# Adafruit_2_9in_eInk_FeatherWing.net
KiCad netlist of a schematic drawn in EAGLE
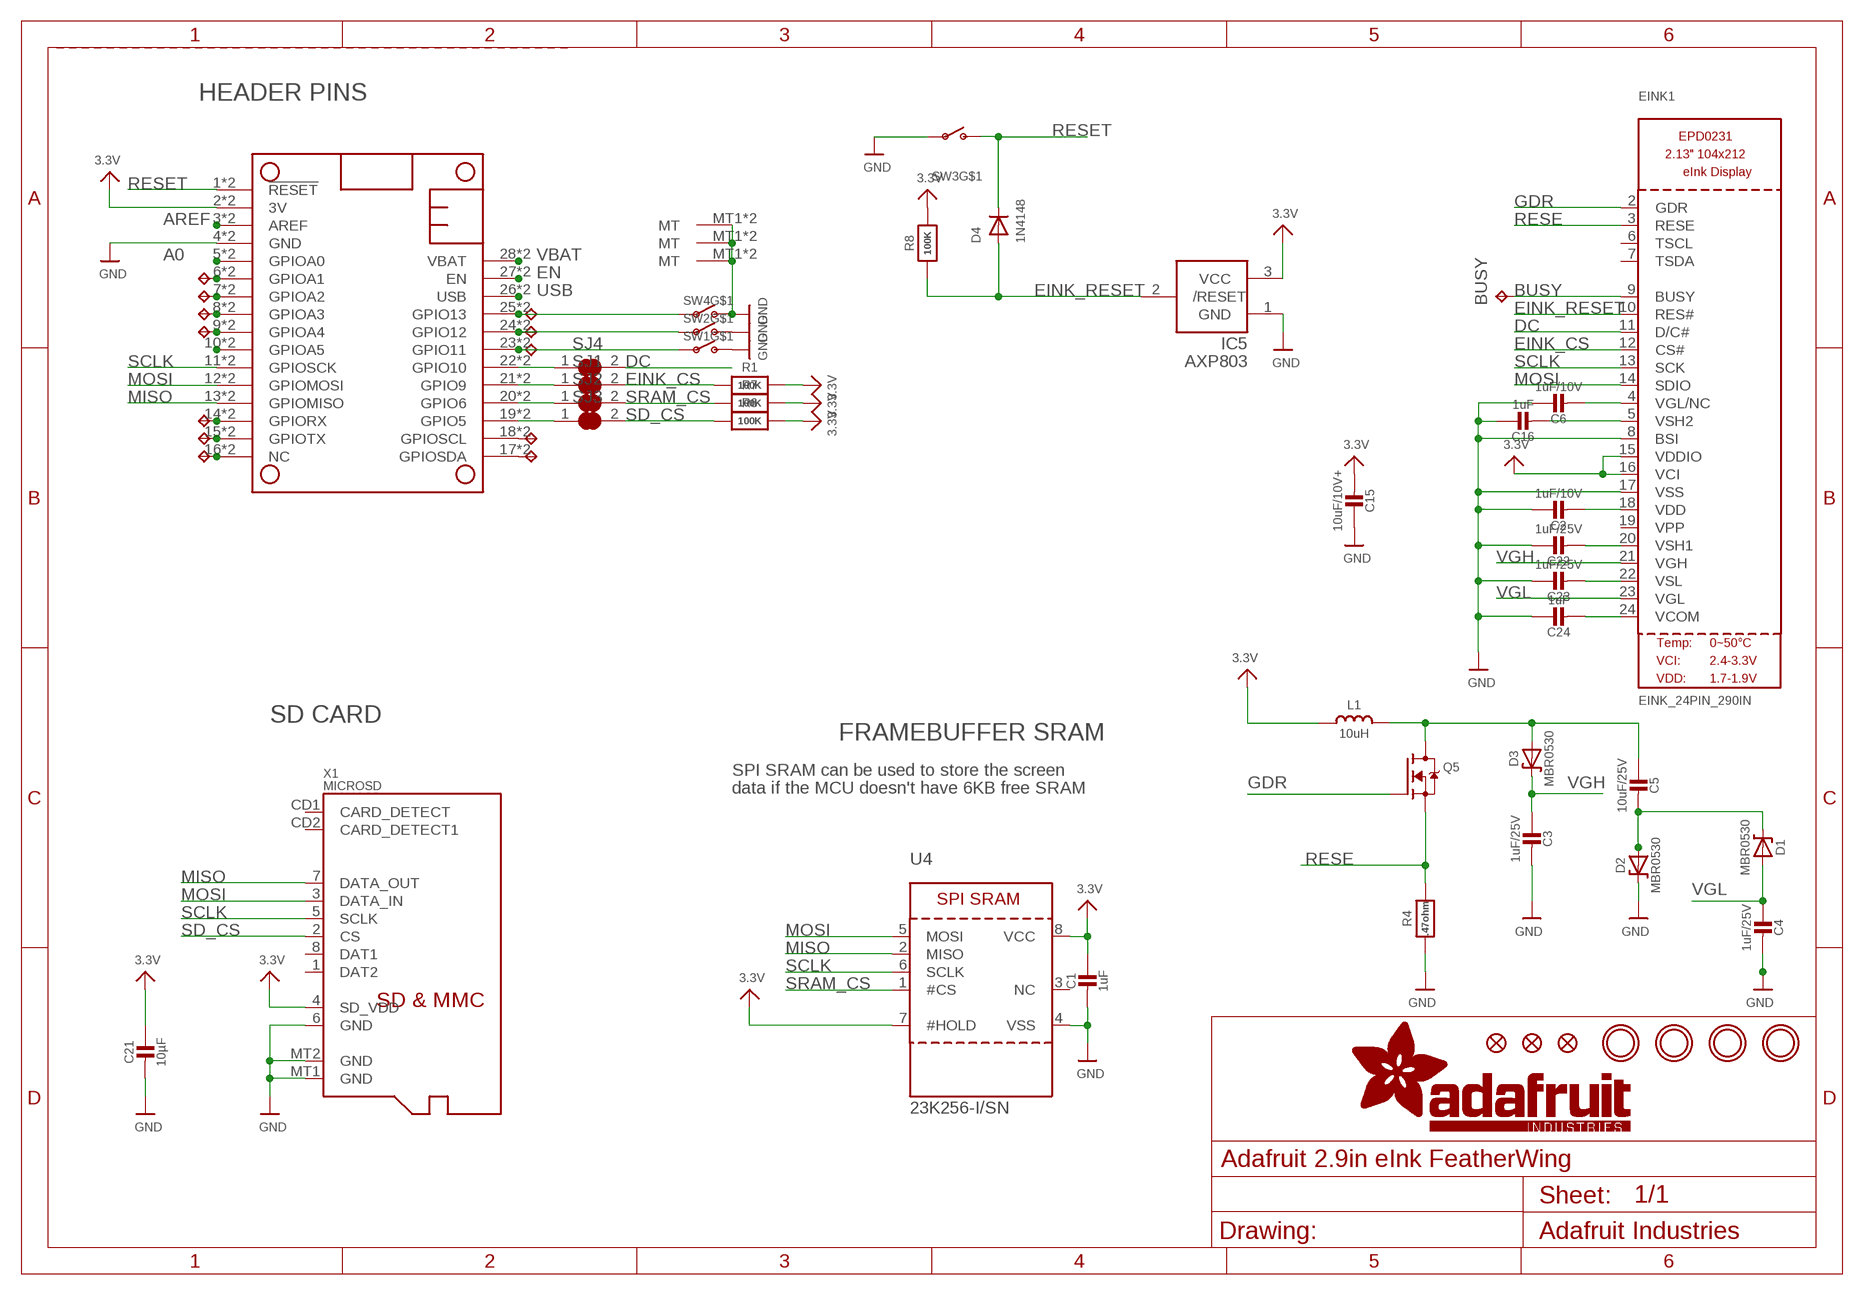
[diagram p0: schematic, sheet 1]

(export (version "E")
  (design (tool "Eeschema 10.0.6"))
  (components
    (comp (ref "BUSY")
      (value "TPTP15SQ")
      (footprint "eagle-import:TP15SQ")
      (libsource (lib "eagle-import") (part "TPTP15SQ"))
    )
    (comp (ref "C1")
      (value "1uF")
      (footprint "eagle-import:0805_10MGAP")
      (fields (field (name "REV") "A"))
      (libsource (lib "eagle-import") (part "CAP_CERAMIC0805_10MGAP"))
    )
    (comp (ref "C2")
      (value "1uF/10V")
      (footprint "eagle-import:0805-NO")
      (libsource (lib "eagle-import") (part "CAP_CERAMIC0805-NOOUTLINE"))
    )
    (comp (ref "C3")
      (value "1uF/25V")
      (footprint "eagle-import:0805-NO")
      (libsource (lib "eagle-import") (part "CAP_CERAMIC0805-NOOUTLINE"))
    )
    (comp (ref "C4")
      (value "1uF/25V")
      (footprint "eagle-import:0805-NO")
      (libsource (lib "eagle-import") (part "CAP_CERAMIC0805-NOOUTLINE"))
    )
    (comp (ref "C5")
      (value "10uF/25V")
      (footprint "eagle-import:0805-NO")
      (libsource (lib "eagle-import") (part "CAP_CERAMIC0805-NOOUTLINE"))
    )
    (comp (ref "C6")
      (value "1uF/10V")
      (footprint "eagle-import:0805-NO")
      (libsource (lib "eagle-import") (part "CAP_CERAMIC0805-NOOUTLINE"))
    )
    (comp (ref "C15")
      (value "10uF/10V+")
      (footprint "eagle-import:0805-NO")
      (libsource (lib "eagle-import") (part "CAP_CERAMIC0805-NOOUTLINE"))
    )
    (comp (ref "C16")
      (value "1uF")
      (footprint "eagle-import:0805-NO")
      (libsource (lib "eagle-import") (part "CAP_CERAMIC0805-NOOUTLINE"))
    )
    (comp (ref "C21")
      (value "10µF")
      (footprint "eagle-import:0805-NO")
      (libsource (lib "eagle-import") (part "CAP_CERAMIC0805-NOOUTLINE"))
    )
    (comp (ref "C22")
      (value "1uF/25V")
      (footprint "eagle-import:0805-NO")
      (libsource (lib "eagle-import") (part "CAP_CERAMIC0805-NOOUTLINE"))
    )
    (comp (ref "C23")
      (value "1uF/25V")
      (footprint "eagle-import:0805-NO")
      (libsource (lib "eagle-import") (part "CAP_CERAMIC0805-NOOUTLINE"))
    )
    (comp (ref "C24")
      (value "1uF")
      (footprint "eagle-import:0805-NO")
      (libsource (lib "eagle-import") (part "CAP_CERAMIC0805-NOOUTLINE"))
    )
    (comp (ref "D1")
      (value "MBR0530")
      (footprint "eagle-import:SOD-123")
      (libsource (lib "eagle-import") (part "DIODE-SCHOTTKYSOD-123"))
    )
    (comp (ref "D2")
      (value "MBR0530")
      (footprint "eagle-import:SOD-123")
      (libsource (lib "eagle-import") (part "DIODE-SCHOTTKYSOD-123"))
    )
    (comp (ref "D3")
      (value "MBR0530")
      (footprint "eagle-import:SOD-123")
      (libsource (lib "eagle-import") (part "DIODE-SCHOTTKYSOD-123"))
    )
    (comp (ref "D4")
      (value "1N4148")
      (footprint "eagle-import:SOD-323F")
      (libsource (lib "eagle-import") (part "DIODESOD-323F"))
    )
    (comp (ref "EINK1")
      (value "EINK_24PIN_290IN")
      (footprint "eagle-import:EINK_290IN")
      (libsource (lib "eagle-import") (part "EINK_24PIN_290IN"))
    )
    (comp (ref "FID1")
      (value "FIDUCIAL_1MM")
      (footprint "eagle-import:FIDUCIAL_1MM")
      (libsource (lib "eagle-import") (part "FIDUCIAL_1MM"))
    )
    (comp (ref "FID2")
      (value "FIDUCIAL_1MM")
      (footprint "eagle-import:FIDUCIAL_1MM")
      (libsource (lib "eagle-import") (part "FIDUCIAL_1MM"))
    )
    (comp (ref "FID3")
      (value "FIDUCIAL_1MM")
      (footprint "eagle-import:FIDUCIAL_1MM")
      (libsource (lib "eagle-import") (part "FIDUCIAL_1MM"))
    )
    (comp (ref "IC5")
      (value "AXP803")
      (footprint "eagle-import:SOT23")
      (libsource (lib "eagle-import") (part "AXP083-SAG"))
    )
    (comp (ref "L1")
      (value "10uH")
      (footprint "eagle-import:INDUCTOR_4X4MM_NR401")
      (libsource (lib "eagle-import") (part "INDUCTORNR401"))
    )
    (comp (ref "MS1")
      (value "FEATHERWING_SMTDUALNOHOLES")
      (footprint "eagle-import:FEATHERWING_SMT_NOHOLES")
      (libsource (lib "eagle-import") (part "FEATHERWING_SMTDUALNOHOLES"))
    )
    (comp (ref "Q5")
      (value "IRLML0100")
      (footprint "eagle-import:SOT23-3")
      (libsource (lib "eagle-import") (part "IRLML2060TRPBF"))
    )
    (comp (ref "R1")
      (value "100K")
      (footprint "eagle-import:0603-NO")
      (libsource (lib "eagle-import") (part "RESISTOR_0603_NOOUT"))
    )
    (comp (ref "R4")
      (value ".47ohm")
      (footprint "eagle-import:0805_10MGAP")
      (libsource (lib "eagle-import") (part "RESISTOR0805_10MGAP"))
    )
    (comp (ref "R6")
      (value "100K")
      (footprint "eagle-import:0603-NO")
      (libsource (lib "eagle-import") (part "RESISTOR_0603_NOOUT"))
    )
    (comp (ref "R7")
      (value "100K")
      (footprint "eagle-import:0603-NO")
      (libsource (lib "eagle-import") (part "RESISTOR_0603_NOOUT"))
    )
    (comp (ref "R8")
      (value "100K")
      (footprint "eagle-import:0603-NO")
      (libsource (lib "eagle-import") (part "RESISTOR_0603_NOOUT"))
    )
    (comp (ref "SJ1")
      (value "SOLDERJUMPER_CLOSED")
      (footprint "eagle-import:SOLDERJUMPER_CLOSEDWIRE")
      (libsource (lib "eagle-import") (part "SOLDERJUMPER_CLOSED"))
    )
    (comp (ref "SJ2")
      (value "SOLDERJUMPER_CLOSED")
      (footprint "eagle-import:SOLDERJUMPER_CLOSEDWIRE")
      (libsource (lib "eagle-import") (part "SOLDERJUMPER_CLOSED"))
    )
    (comp (ref "SJ3")
      (value "SOLDERJUMPER_CLOSED")
      (footprint "eagle-import:SOLDERJUMPER_CLOSEDWIRE")
      (libsource (lib "eagle-import") (part "SOLDERJUMPER_CLOSED"))
    )
    (comp (ref "SJ4")
      (value "SOLDERJUMPER_CLOSED")
      (footprint "eagle-import:SOLDERJUMPER_CLOSEDWIRE")
      (libsource (lib "eagle-import") (part "SOLDERJUMPER_CLOSED"))
    )
    (comp (ref "SW1")
      (value "SWITCH_SPST_TACT_RA")
      (footprint "eagle-import:SPST_TACTILE_RA")
      (libsource (lib "eagle-import") (part "SWITCH_SPST_TACT_RA"))
    )
    (comp (ref "SW2")
      (value "SWITCH_SPST_TACT_RA")
      (footprint "eagle-import:SPST_TACTILE_RA")
      (libsource (lib "eagle-import") (part "SWITCH_SPST_TACT_RA"))
    )
    (comp (ref "SW3")
      (value "SWITCH_SPST_TACT_RA")
      (footprint "eagle-import:SPST_TACTILE_RA")
      (libsource (lib "eagle-import") (part "SWITCH_SPST_TACT_RA"))
    )
    (comp (ref "SW4")
      (value "SWITCH_SPST_TACT_RA")
      (footprint "eagle-import:SPST_TACTILE_RA")
      (libsource (lib "eagle-import") (part "SWITCH_SPST_TACT_RA"))
    )
    (comp (ref "TP1")
      (value "TPTP15SQ")
      (footprint "eagle-import:TP15SQ")
      (libsource (lib "eagle-import") (part "TPTP15SQ"))
    )
    (comp (ref "TP2")
      (value "TPTP15SQ")
      (footprint "eagle-import:TP15SQ")
      (libsource (lib "eagle-import") (part "TPTP15SQ"))
    )
    (comp (ref "TP3")
      (value "TPTP15SQ")
      (footprint "eagle-import:TP15SQ")
      (libsource (lib "eagle-import") (part "TPTP15SQ"))
    )
    (comp (ref "TP4")
      (value "TPTP15SQ")
      (footprint "eagle-import:TP15SQ")
      (libsource (lib "eagle-import") (part "TPTP15SQ"))
    )
    (comp (ref "TP5")
      (value "TPTP15SQ")
      (footprint "eagle-import:TP15SQ")
      (libsource (lib "eagle-import") (part "TPTP15SQ"))
    )
    (comp (ref "TP6")
      (value "TPTP15SQ")
      (footprint "eagle-import:TP15SQ")
      (libsource (lib "eagle-import") (part "TPTP15SQ"))
    )
    (comp (ref "TP7")
      (value "TPTP15SQ")
      (footprint "eagle-import:TP15SQ")
      (libsource (lib "eagle-import") (part "TPTP15SQ"))
    )
    (comp (ref "TP8")
      (value "TPTP15SQ")
      (footprint "eagle-import:TP15SQ")
      (libsource (lib "eagle-import") (part "TPTP15SQ"))
    )
    (comp (ref "TP9")
      (value "TPTP15SQ")
      (footprint "eagle-import:TP15SQ")
      (libsource (lib "eagle-import") (part "TPTP15SQ"))
    )
    (comp (ref "TP11")
      (value "TPTP15SQ")
      (footprint "eagle-import:TP15SQ")
      (libsource (lib "eagle-import") (part "TPTP15SQ"))
    )
    (comp (ref "TP12")
      (value "TPTP15SQ")
      (footprint "eagle-import:TP15SQ")
      (libsource (lib "eagle-import") (part "TPTP15SQ"))
    )
    (comp (ref "TP13")
      (value "TPTP15SQ")
      (footprint "eagle-import:TP15SQ")
      (libsource (lib "eagle-import") (part "TPTP15SQ"))
    )
    (comp (ref "U$3")
      (value "MOUNTINGHOLE2.5")
      (footprint "eagle-import:MOUNTINGHOLE_2.5_PLATED")
      (libsource (lib "eagle-import") (part "MOUNTINGHOLE2.5"))
    )
    (comp (ref "U$4")
      (value "MOUNTINGHOLE2.5")
      (footprint "eagle-import:MOUNTINGHOLE_2.5_PLATED")
      (libsource (lib "eagle-import") (part "MOUNTINGHOLE2.5"))
    )
    (comp (ref "U$5")
      (value "MOUNTINGHOLE2.5")
      (footprint "eagle-import:MOUNTINGHOLE_2.5_PLATED")
      (libsource (lib "eagle-import") (part "MOUNTINGHOLE2.5"))
    )
    (comp (ref "U$6")
      (value "MOUNTINGHOLE2.5")
      (footprint "eagle-import:MOUNTINGHOLE_2.5_PLATED")
      (libsource (lib "eagle-import") (part "MOUNTINGHOLE2.5"))
    )
    (comp (ref "U4")
      (value "23K256-I/SN")
      (footprint "eagle-import:SOIC8_150MIL")
      (libsource (lib "eagle-import") (part "SRAM_SPI_SOIC8"))
    )
    (comp (ref "X1")
      (value "MICROSD")
      (footprint "eagle-import:MICROSD")
      (libsource (lib "eagle-import") (part "MICROSD"))
    )
  )
  (nets
    (net (code "3") (name "/A0") (class "Default")
      (node (ref "MS1") (pin "5") (pinfunction "GPIOA0_5") (pintype "bidirectional"))
      (node (ref "MS1") (pin "5B") (pinfunction "GPIOA0_5B") (pintype "bidirectional"))
    )
    (net (code "4") (name "/AREF") (class "Default")
      (node (ref "MS1") (pin "3") (pinfunction "AREF_3") (pintype "passive"))
      (node (ref "MS1") (pin "3B") (pinfunction "AREF_3B") (pintype "passive"))
    )
    (net (code "5") (name "/BUSY") (class "Default")
      (node (ref "BUSY") (pin "TP") (pinfunction "TP_TP") (pintype "input"))
      (node (ref "EINK1") (pin "9") (pinfunction "BUSY_9") (pintype "output"))
    )
    (net (code "6") (name "/DC") (class "Default")
      (node (ref "EINK1") (pin "11") (pinfunction "D/C#_11") (pintype "input"))
      (node (ref "SJ4") (pin "2") (pinfunction "2_2") (pintype "passive"))
    )
    (net (code "8") (name "/EINK_CS") (class "Default")
      (node (ref "EINK1") (pin "12") (pinfunction "CS#_12") (pintype "input"))
      (node (ref "R1") (pin "1") (pinfunction "1_1") (pintype "passive"))
      (node (ref "SJ1") (pin "2") (pinfunction "2_2") (pintype "passive"))
    )
    (net (code "9") (name "/EINK_RESET") (class "Default")
      (node (ref "D4") (pin "A") (pinfunction "A_A") (pintype "passive"))
      (node (ref "EINK1") (pin "10") (pinfunction "RES#_10") (pintype "input"))
      (node (ref "IC5") (pin "2") (pinfunction "/RESET_2") (pintype "output"))
      (node (ref "R8") (pin "1") (pinfunction "1_1") (pintype "passive"))
    )
    (net (code "10") (name "/EN") (class "Default")
      (node (ref "MS1") (pin "27") (pinfunction "EN_27") (pintype "passive"))
      (node (ref "MS1") (pin "27B") (pinfunction "EN_27B") (pintype "passive"))
    )
    (net (code "11") (name "/GDR") (class "Default")
      (node (ref "EINK1") (pin "2") (pinfunction "GDR_2") (pintype "output"))
      (node (ref "Q5") (pin "1") (pinfunction "G_1") (pintype "bidirectional"))
    )
    (net (code "12") (name "/MISO") (class "Default")
      (node (ref "MS1") (pin "13") (pinfunction "GPIOMISO_13") (pintype "bidirectional"))
      (node (ref "MS1") (pin "13B") (pinfunction "GPIOMISO_13B") (pintype "bidirectional"))
      (node (ref "U4") (pin "2") (pinfunction "MISO_2") (pintype "output"))
      (node (ref "X1") (pin "7") (pinfunction "DATA_OUT_7") (pintype "output"))
    )
    (net (code "13") (name "/MOSI") (class "Default")
      (node (ref "EINK1") (pin "14") (pinfunction "SDIO_14") (pintype "bidirectional"))
      (node (ref "MS1") (pin "12") (pinfunction "GPIOMOSI_12") (pintype "bidirectional"))
      (node (ref "MS1") (pin "12B") (pinfunction "GPIOMOSI_12B") (pintype "bidirectional"))
      (node (ref "U4") (pin "5") (pinfunction "MOSI_5") (pintype "input"))
      (node (ref "X1") (pin "3") (pinfunction "DATA_IN_3") (pintype "input"))
    )
    (net (code "14") (name "/RESE") (class "Default")
      (node (ref "EINK1") (pin "3") (pinfunction "RESE_3") (pintype "input"))
      (node (ref "Q5") (pin "2") (pinfunction "S_2") (pintype "bidirectional"))
      (node (ref "R4") (pin "1") (pinfunction "1_1") (pintype "passive"))
    )
    (net (code "15") (name "/RESET") (class "Default")
      (node (ref "D4") (pin "C") (pinfunction "C_C") (pintype "passive"))
      (node (ref "MS1") (pin "1") (pinfunction "~{RESET}_1") (pintype "input"))
      (node (ref "MS1") (pin "1B") (pinfunction "~{RESET}_1B") (pintype "input"))
      (node (ref "SW3") (pin "2") (pinfunction "S_2") (pintype "passive"))
    )
    (net (code "18") (name "/SCLK") (class "Default")
      (node (ref "EINK1") (pin "13") (pinfunction "SCK_13") (pintype "bidirectional"))
      (node (ref "MS1") (pin "11") (pinfunction "GPIOSCK_11") (pintype "bidirectional"))
      (node (ref "MS1") (pin "11B") (pinfunction "GPIOSCK_11B") (pintype "bidirectional"))
      (node (ref "U4") (pin "6") (pinfunction "SCLK_6") (pintype "input"))
      (node (ref "X1") (pin "5") (pinfunction "SCLK_5") (pintype "input"))
    )
    (net (code "19") (name "/SD_CS") (class "Default")
      (node (ref "R6") (pin "1") (pinfunction "1_1") (pintype "passive"))
      (node (ref "SJ3") (pin "2") (pinfunction "2_2") (pintype "passive"))
      (node (ref "X1") (pin "2") (pinfunction "CS_2") (pintype "input"))
    )
    (net (code "20") (name "/SRAM_CS") (class "Default")
      (node (ref "R7") (pin "1") (pinfunction "1_1") (pintype "passive"))
      (node (ref "SJ2") (pin "2") (pinfunction "2_2") (pintype "passive"))
      (node (ref "U4") (pin "1") (pinfunction "#CS_1") (pintype "input"))
    )
    (net (code "21") (name "/USB") (class "Default")
      (node (ref "MS1") (pin "26") (pinfunction "USB_26") (pintype "power_in"))
      (node (ref "MS1") (pin "26B") (pinfunction "USB_26B") (pintype "power_in"))
    )
    (net (code "22") (name "/VBAT") (class "Default")
      (node (ref "MS1") (pin "28") (pinfunction "VBAT_28") (pintype "power_in"))
      (node (ref "MS1") (pin "28B") (pinfunction "VBAT_28B") (pintype "power_in"))
    )
    (net (code "23") (name "/VGH") (class "Default")
      (node (ref "C3") (pin "1") (pinfunction "1_1") (pintype "passive"))
      (node (ref "D3") (pin "C") (pinfunction "C_C") (pintype "passive"))
      (node (ref "EINK1") (pin "21") (pinfunction "VGH_21") (pintype "passive"))
    )
    (net (code "24") (name "/VGL") (class "Default")
      (node (ref "C4") (pin "1") (pinfunction "1_1") (pintype "passive"))
      (node (ref "D1") (pin "A") (pinfunction "A_A") (pintype "passive"))
      (node (ref "EINK1") (pin "23") (pinfunction "VGL_23") (pintype "passive"))
    )
    (net (code "25") (name "3.3V") (class "Default")
      (node (ref "C1") (pin "1") (pinfunction "1_1") (pintype "passive"))
      (node (ref "C15") (pin "2") (pinfunction "2_2") (pintype "passive"))
      (node (ref "C21") (pin "1") (pinfunction "1_1") (pintype "passive"))
      (node (ref "EINK1") (pin "15") (pinfunction "VDDIO_15") (pintype "power_in"))
      (node (ref "EINK1") (pin "16") (pinfunction "VCI_16") (pintype "power_in"))
      (node (ref "IC5") (pin "3") (pinfunction "VCC_3") (pintype "power_in"))
      (node (ref "L1") (pin "P$2") (pinfunction "2_P$2") (pintype "passive"))
      (node (ref "MS1") (pin "2") (pinfunction "3V_2") (pintype "power_in"))
      (node (ref "MS1") (pin "2B") (pinfunction "3V_2B") (pintype "power_in"))
      (node (ref "R1") (pin "2") (pinfunction "2_2") (pintype "passive"))
      (node (ref "R6") (pin "2") (pinfunction "2_2") (pintype "passive"))
      (node (ref "R7") (pin "2") (pinfunction "2_2") (pintype "passive"))
      (node (ref "R8") (pin "2") (pinfunction "2_2") (pintype "passive"))
      (node (ref "U4") (pin "7") (pinfunction "#HOLD_7") (pintype "input"))
      (node (ref "U4") (pin "8") (pinfunction "VCC_8") (pintype "power_in"))
      (node (ref "X1") (pin "4") (pinfunction "SD_VDD_4") (pintype "power_in"))
    )
    (net (code "26") (name "GND") (class "Default")
      (node (ref "C1") (pin "2") (pinfunction "2_2") (pintype "passive"))
      (node (ref "C15") (pin "1") (pinfunction "1_1") (pintype "passive"))
      (node (ref "C16") (pin "1") (pinfunction "1_1") (pintype "passive"))
      (node (ref "C2") (pin "1") (pinfunction "1_1") (pintype "passive"))
      (node (ref "C21") (pin "2") (pinfunction "2_2") (pintype "passive"))
      (node (ref "C22") (pin "1") (pinfunction "1_1") (pintype "passive"))
      (node (ref "C23") (pin "1") (pinfunction "1_1") (pintype "passive"))
      (node (ref "C24") (pin "1") (pinfunction "1_1") (pintype "passive"))
      (node (ref "C3") (pin "2") (pinfunction "2_2") (pintype "passive"))
      (node (ref "C4") (pin "2") (pinfunction "2_2") (pintype "passive"))
      (node (ref "C6") (pin "1") (pinfunction "1_1") (pintype "passive"))
      (node (ref "D2") (pin "C") (pinfunction "C_C") (pintype "passive"))
      (node (ref "EINK1") (pin "17") (pinfunction "VSS_17") (pintype "power_in"))
      (node (ref "EINK1") (pin "8") (pinfunction "BSI_8") (pintype "input"))
      (node (ref "IC5") (pin "1") (pinfunction "GND_1") (pintype "power_in"))
      (node (ref "MS1") (pin "4") (pinfunction "GND_4") (pintype "power_in"))
      (node (ref "MS1") (pin "4B") (pinfunction "GND_4B") (pintype "power_in"))
      (node (ref "R4") (pin "2") (pinfunction "2_2") (pintype "passive"))
      (node (ref "SW1") (pin "2") (pinfunction "S_2") (pintype "passive"))
      (node (ref "SW1") (pin "MT1") (pinfunction "MT_MT1") (pintype "bidirectional"))
      (node (ref "SW1") (pin "MT2") (pinfunction "MT_MT2") (pintype "bidirectional"))
      (node (ref "SW2") (pin "2") (pinfunction "S_2") (pintype "passive"))
      (node (ref "SW2") (pin "MT1") (pinfunction "MT_MT1") (pintype "bidirectional"))
      (node (ref "SW2") (pin "MT2") (pinfunction "MT_MT2") (pintype "bidirectional"))
      (node (ref "SW3") (pin "1") (pinfunction "P_1") (pintype "passive"))
      (node (ref "SW4") (pin "2") (pinfunction "S_2") (pintype "passive"))
      (node (ref "SW4") (pin "MT1") (pinfunction "MT_MT1") (pintype "bidirectional"))
      (node (ref "SW4") (pin "MT2") (pinfunction "MT_MT2") (pintype "bidirectional"))
      (node (ref "U4") (pin "4") (pinfunction "VSS_4") (pintype "power_in"))
      (node (ref "X1") (pin "6") (pinfunction "GND_6") (pintype "power_in"))
      (node (ref "X1") (pin "MT1") (pinfunction "GND_MT1") (pintype "power_in"))
      (node (ref "X1") (pin "MT2") (pinfunction "GND_MT2") (pintype "power_in"))
    )
    (net (code "27") (name "Net-(C5-Pad2)") (class "Default")
      (node (ref "C5") (pin "2") (pinfunction "2_2") (pintype "passive"))
      (node (ref "D1") (pin "C") (pinfunction "C_C") (pintype "passive"))
      (node (ref "D2") (pin "A") (pinfunction "A_A") (pintype "passive"))
    )
    (net (code "28") (name "Net-(EINK1-VCOM)") (class "Default")
      (node (ref "C24") (pin "2") (pinfunction "2_2") (pintype "passive"))
      (node (ref "EINK1") (pin "24") (pinfunction "VCOM_24") (pintype "passive"))
    )
    (net (code "29") (name "Net-(EINK1-VDD)") (class "Default")
      (node (ref "C2") (pin "2") (pinfunction "2_2") (pintype "passive"))
      (node (ref "EINK1") (pin "18") (pinfunction "VDD_18") (pintype "passive"))
    )
    (net (code "30") (name "Net-(EINK1-VGL{slash}NC)") (class "Default")
      (node (ref "C6") (pin "2") (pinfunction "2_2") (pintype "passive"))
      (node (ref "EINK1") (pin "4") (pinfunction "VGL/NC_4") (pintype "bidirectional"))
    )
    (net (code "31") (name "Net-(EINK1-VSH1)") (class "Default")
      (node (ref "C22") (pin "2") (pinfunction "2_2") (pintype "passive"))
      (node (ref "EINK1") (pin "20") (pinfunction "VSH1_20") (pintype "passive"))
    )
    (net (code "32") (name "Net-(EINK1-VSH2)") (class "Default")
      (node (ref "C16") (pin "2") (pinfunction "2_2") (pintype "passive"))
      (node (ref "EINK1") (pin "5") (pinfunction "VSH2_5") (pintype "passive"))
    )
    (net (code "33") (name "Net-(EINK1-VSL)") (class "Default")
      (node (ref "C23") (pin "2") (pinfunction "2_2") (pintype "passive"))
      (node (ref "EINK1") (pin "22") (pinfunction "VSL_22") (pintype "passive"))
    )
    (net (code "34") (name "Net-(L1-1)") (class "Default")
      (node (ref "C5") (pin "1") (pinfunction "1_1") (pintype "passive"))
      (node (ref "D3") (pin "A") (pinfunction "A_A") (pintype "passive"))
      (node (ref "L1") (pin "P$1") (pinfunction "1_P$1") (pintype "passive"))
      (node (ref "Q5") (pin "3") (pinfunction "D_3") (pintype "bidirectional"))
    )
    (net (code "35") (name "Net-(MS1-GPIO5-Pad19)") (class "Default")
      (node (ref "MS1") (pin "19") (pinfunction "GPIO5_19") (pintype "bidirectional"))
      (node (ref "MS1") (pin "19B") (pinfunction "GPIO5_19B") (pintype "bidirectional"))
      (node (ref "SJ3") (pin "1") (pinfunction "1_1") (pintype "passive"))
    )
    (net (code "36") (name "Net-(MS1-GPIO6-Pad20)") (class "Default")
      (node (ref "MS1") (pin "20") (pinfunction "GPIO6_20") (pintype "bidirectional"))
      (node (ref "MS1") (pin "20B") (pinfunction "GPIO6_20B") (pintype "bidirectional"))
      (node (ref "SJ2") (pin "1") (pinfunction "1_1") (pintype "passive"))
    )
    (net (code "37") (name "Net-(MS1-GPIO9-Pad21)") (class "Default")
      (node (ref "MS1") (pin "21") (pinfunction "GPIO9_21") (pintype "bidirectional"))
      (node (ref "MS1") (pin "21B") (pinfunction "GPIO9_21B") (pintype "bidirectional"))
      (node (ref "SJ1") (pin "1") (pinfunction "1_1") (pintype "passive"))
    )
    (net (code "38") (name "Net-(MS1-GPIO10-Pad22)") (class "Default")
      (node (ref "MS1") (pin "22") (pinfunction "GPIO10_22") (pintype "bidirectional"))
      (node (ref "MS1") (pin "22B") (pinfunction "GPIO10_22B") (pintype "bidirectional"))
      (node (ref "SJ4") (pin "1") (pinfunction "1_1") (pintype "passive"))
    )
    (net (code "39") (name "Net-(MS1-GPIOA1-Pad6)") (class "Default")
      (node (ref "MS1") (pin "6") (pinfunction "GPIOA1_6") (pintype "bidirectional"))
      (node (ref "MS1") (pin "6B") (pinfunction "GPIOA1_6B") (pintype "bidirectional"))
      (node (ref "TP6") (pin "TP") (pinfunction "TP_TP") (pintype "input"))
    )
    (net (code "40") (name "Net-(MS1-GPIOA2-Pad7)") (class "Default")
      (node (ref "MS1") (pin "7") (pinfunction "GPIOA2_7") (pintype "bidirectional"))
      (node (ref "MS1") (pin "7B") (pinfunction "GPIOA2_7B") (pintype "bidirectional"))
      (node (ref "TP7") (pin "TP") (pinfunction "TP_TP") (pintype "input"))
    )
    (net (code "41") (name "Net-(MS1-GPIOA3-Pad8)") (class "Default")
      (node (ref "MS1") (pin "8") (pinfunction "GPIOA3_8") (pintype "bidirectional"))
      (node (ref "MS1") (pin "8B") (pinfunction "GPIOA3_8B") (pintype "bidirectional"))
      (node (ref "TP8") (pin "TP") (pinfunction "TP_TP") (pintype "input"))
    )
    (net (code "42") (name "Net-(MS1-GPIOA4-Pad9)") (class "Default")
      (node (ref "MS1") (pin "9") (pinfunction "GPIOA4_9") (pintype "bidirectional"))
      (node (ref "MS1") (pin "9B") (pinfunction "GPIOA4_9B") (pintype "bidirectional"))
      (node (ref "TP9") (pin "TP") (pinfunction "TP_TP") (pintype "input"))
    )
    (net (code "43") (name "Net-(MS1-GPIOA5-Pad10)") (class "Default")
      (node (ref "MS1") (pin "10") (pinfunction "GPIOA5_10") (pintype "bidirectional"))
      (node (ref "MS1") (pin "10B") (pinfunction "GPIOA5_10B") (pintype "bidirectional"))
    )
    (net (code "44") (name "Net-(MS1-GPIORX-Pad14)") (class "Default")
      (node (ref "MS1") (pin "14") (pinfunction "GPIORX_14") (pintype "bidirectional"))
      (node (ref "MS1") (pin "14B") (pinfunction "GPIORX_14B") (pintype "bidirectional"))
      (node (ref "TP11") (pin "TP") (pinfunction "TP_TP") (pintype "input"))
    )
    (net (code "45") (name "Net-(MS1-GPIOSCL-Pad18)") (class "Default")
      (node (ref "MS1") (pin "18") (pinfunction "GPIOSCL_18") (pintype "bidirectional"))
      (node (ref "MS1") (pin "18B") (pinfunction "GPIOSCL_18B") (pintype "bidirectional"))
      (node (ref "TP3") (pin "TP") (pinfunction "TP_TP") (pintype "input"))
    )
    (net (code "46") (name "Net-(MS1-GPIOSDA-Pad17)") (class "Default")
      (node (ref "MS1") (pin "17") (pinfunction "GPIOSDA_17") (pintype "bidirectional"))
      (node (ref "MS1") (pin "17B") (pinfunction "GPIOSDA_17B") (pintype "bidirectional"))
      (node (ref "TP4") (pin "TP") (pinfunction "TP_TP") (pintype "input"))
    )
    (net (code "47") (name "Net-(MS1-GPIOTX-Pad15)") (class "Default")
      (node (ref "MS1") (pin "15") (pinfunction "GPIOTX_15") (pintype "bidirectional"))
      (node (ref "MS1") (pin "15B") (pinfunction "GPIOTX_15B") (pintype "bidirectional"))
      (node (ref "TP12") (pin "TP") (pinfunction "TP_TP") (pintype "input"))
    )
    (net (code "48") (name "Net-(MS1-NC-Pad16)") (class "Default")
      (node (ref "MS1") (pin "16") (pinfunction "NC_16") (pintype "passive"))
      (node (ref "MS1") (pin "16B") (pinfunction "NC_16B") (pintype "passive"))
      (node (ref "TP13") (pin "TP") (pinfunction "TP_TP") (pintype "input"))
    )
    (net (code "49") (name "Net-(SW1A-P)") (class "Default")
      (node (ref "MS1") (pin "23") (pinfunction "GPIO11_23") (pintype "bidirectional"))
      (node (ref "MS1") (pin "23B") (pinfunction "GPIO11_23B") (pintype "bidirectional"))
      (node (ref "SW1") (pin "1") (pinfunction "P_1") (pintype "passive"))
      (node (ref "TP1") (pin "TP") (pinfunction "TP_TP") (pintype "input"))
    )
    (net (code "50") (name "Net-(SW2A-P)") (class "Default")
      (node (ref "MS1") (pin "24") (pinfunction "GPIO12_24") (pintype "bidirectional"))
      (node (ref "MS1") (pin "24B") (pinfunction "GPIO12_24B") (pintype "bidirectional"))
      (node (ref "SW2") (pin "1") (pinfunction "P_1") (pintype "passive"))
      (node (ref "TP2") (pin "TP") (pinfunction "TP_TP") (pintype "input"))
    )
    (net (code "51") (name "Net-(SW4A-P)") (class "Default")
      (node (ref "MS1") (pin "25") (pinfunction "GPIO13_25") (pintype "bidirectional"))
      (node (ref "MS1") (pin "25B") (pinfunction "GPIO13_25B") (pintype "bidirectional"))
      (node (ref "SW4") (pin "1") (pinfunction "P_1") (pintype "passive"))
      (node (ref "TP5") (pin "TP") (pinfunction "TP_TP") (pintype "input"))
    )
    (net (code "52") (name "unconnected-(EINK1-TSCL-Pad6)") (class "Default")
      (node (ref "EINK1") (pin "6") (pinfunction "TSCL_6") (pintype "output"))
    )
    (net (code "53") (name "unconnected-(EINK1-TSDA-Pad7)") (class "Default")
      (node (ref "EINK1") (pin "7") (pinfunction "TSDA_7") (pintype "bidirectional"))
    )
    (net (code "54") (name "unconnected-(EINK1-VPP-Pad19)") (class "Default")
      (node (ref "EINK1") (pin "19") (pinfunction "VPP_19") (pintype "passive"))
    )
    (net (code "55") (name "unconnected-(U4-NC-Pad3)") (class "Default")
      (node (ref "U4") (pin "3") (pinfunction "NC_3") (pintype "no_connect"))
    )
    (net (code "56") (name "unconnected-(X1-CARD_DETECT-PadCD1)") (class "Default")
      (node (ref "X1") (pin "CD1") (pinfunction "CARD_DETECT_CD1") (pintype "passive"))
    )
    (net (code "57") (name "unconnected-(X1-CARD_DETECT1-PadCD2)") (class "Default")
      (node (ref "X1") (pin "CD2") (pinfunction "CARD_DETECT1_CD2") (pintype "passive"))
    )
    (net (code "58") (name "unconnected-(X1-DAT1-Pad8)") (class "Default")
      (node (ref "X1") (pin "8") (pinfunction "DAT1_8") (pintype "bidirectional"))
    )
    (net (code "59") (name "unconnected-(X1-DAT2-Pad1)") (class "Default")
      (node (ref "X1") (pin "1") (pinfunction "DAT2_1") (pintype "bidirectional"))
    )
  )
)
